# GDO.net
KiCad netlist of a schematic drawn in Altium Designer
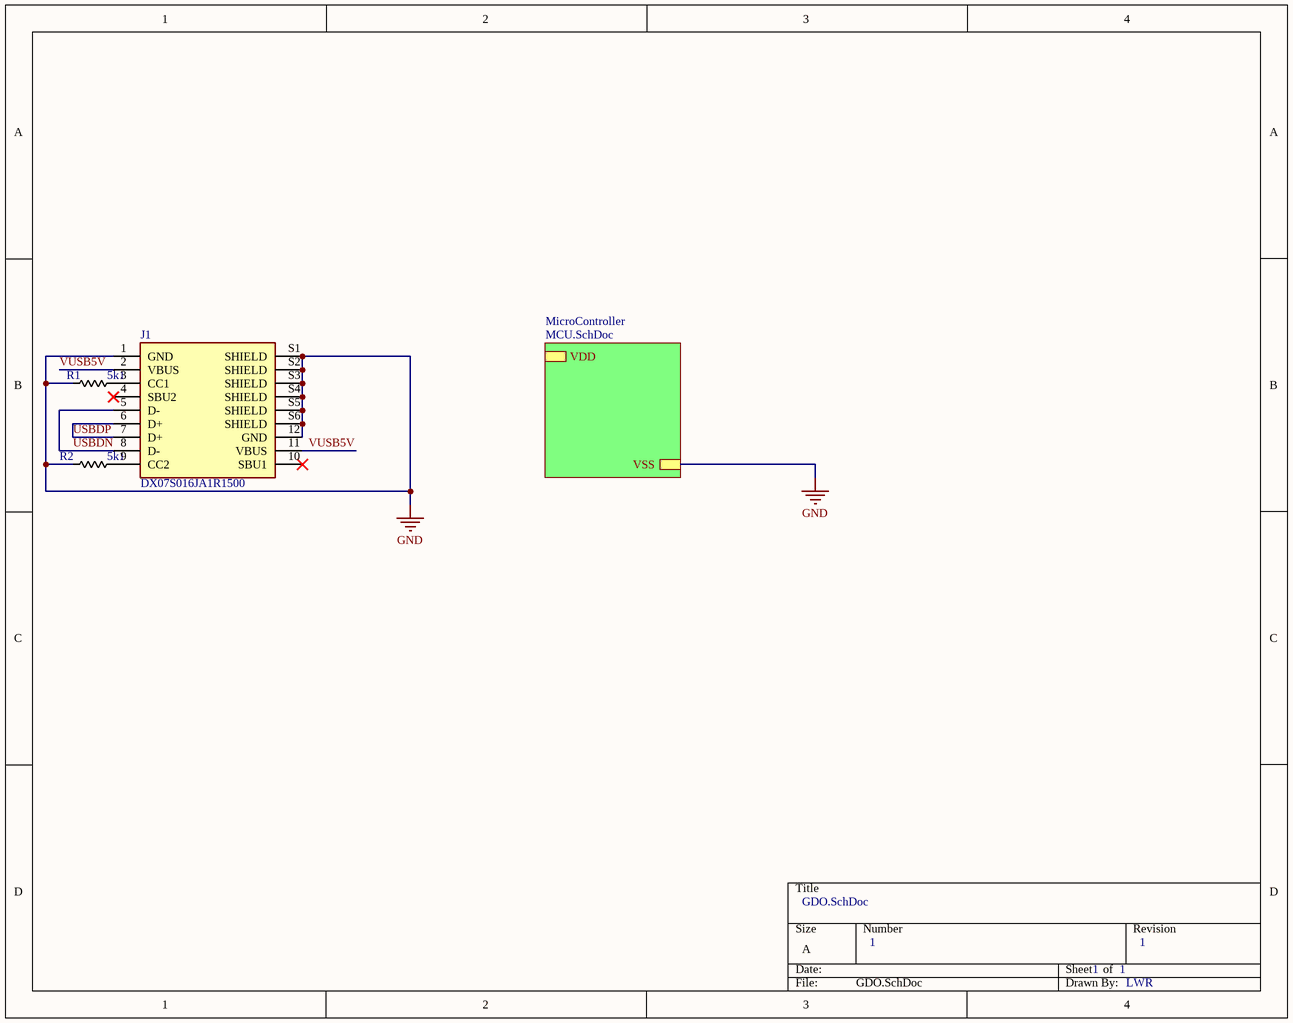
[diagram p0: GDO.SchDoc]

(export (version "E")
  (design (tool "Eeschema 10.0.6"))
  (components
    (comp (ref "J1")
      (value "DX07S016JA1R1500")
      (footprint "GDO:DX07S016JA1R1500")
      (description "USB-C USB 2.0 Receptacle Connector, Right Angle")
      (libsource (lib "GDO") (part "DX07S016JA1R1500"))
    )
    (comp (ref "R1")
      (value "5k1")
      (footprint "GDO:R0603")
      (fields (field (name "TOLERANCE") "<=10%") (field (name "POWER") ">=1/10W"))
      (libsource (lib "GDO") (part "R0603"))
    )
    (comp (ref "R2")
      (value "5k1")
      (footprint "GDO:R0603")
      (fields (field (name "TOLERANCE") "<=10%") (field (name "POWER") ">=1/10W"))
      (libsource (lib "GDO") (part "R0603"))
    )
  )
  (nets
    (net (code "1") (name "/USBDN") (class "Default")
      (node (ref "J1") (pin "5") (pinfunction "D-_5") (pintype "passive"))
      (node (ref "J1") (pin "8") (pinfunction "D-_8") (pintype "passive"))
    )
    (net (code "2") (name "/USBDP") (class "Default")
      (node (ref "J1") (pin "6") (pinfunction "D+_6") (pintype "passive"))
      (node (ref "J1") (pin "7") (pinfunction "D+_7") (pintype "passive"))
    )
    (net (code "4") (name "/VUSB5V") (class "Default")
      (node (ref "J1") (pin "11") (pinfunction "VBUS_11") (pintype "power_in"))
      (node (ref "J1") (pin "2") (pinfunction "VBUS_2") (pintype "power_in"))
    )
    (net (code "5") (name "GND") (class "Default")
      (node (ref "J1") (pin "1") (pinfunction "GND_1") (pintype "power_in"))
      (node (ref "J1") (pin "12") (pinfunction "GND_12") (pintype "power_in"))
      (node (ref "J1") (pin "S1") (pinfunction "SHIELD_S1") (pintype "passive"))
      (node (ref "J1") (pin "S2") (pinfunction "SHIELD_S2") (pintype "passive"))
      (node (ref "J1") (pin "S3") (pinfunction "SHIELD_S3") (pintype "passive"))
      (node (ref "J1") (pin "S4") (pinfunction "SHIELD_S4") (pintype "passive"))
      (node (ref "J1") (pin "S5") (pinfunction "SHIELD_S5") (pintype "passive"))
      (node (ref "J1") (pin "S6") (pinfunction "SHIELD_S6") (pintype "passive"))
      (node (ref "R1") (pin "1") (pinfunction "1_1") (pintype "passive"))
      (node (ref "R2") (pin "1") (pinfunction "1_1") (pintype "passive"))
    )
    (net (code "6") (name "Net-(J1-CC1)") (class "Default")
      (node (ref "J1") (pin "3") (pinfunction "CC1_3") (pintype "passive"))
      (node (ref "R1") (pin "2") (pinfunction "2_2") (pintype "passive"))
    )
    (net (code "7") (name "Net-(J1-CC2)") (class "Default")
      (node (ref "J1") (pin "9") (pinfunction "CC2_9") (pintype "passive"))
      (node (ref "R2") (pin "2") (pinfunction "2_2") (pintype "passive"))
    )
    (net (code "8") (name "unconnected-(J1-SBU1-Pad10)") (class "Default")
      (node (ref "J1") (pin "10") (pinfunction "SBU1_10") (pintype "passive+no_connect"))
    )
    (net (code "9") (name "unconnected-(J1-SBU2-Pad4)") (class "Default")
      (node (ref "J1") (pin "4") (pinfunction "SBU2_4") (pintype "passive+no_connect"))
    )
  )
)
